# PG3_SHEET1.net
KiCad netlist of a schematic drawn in Altium Designer
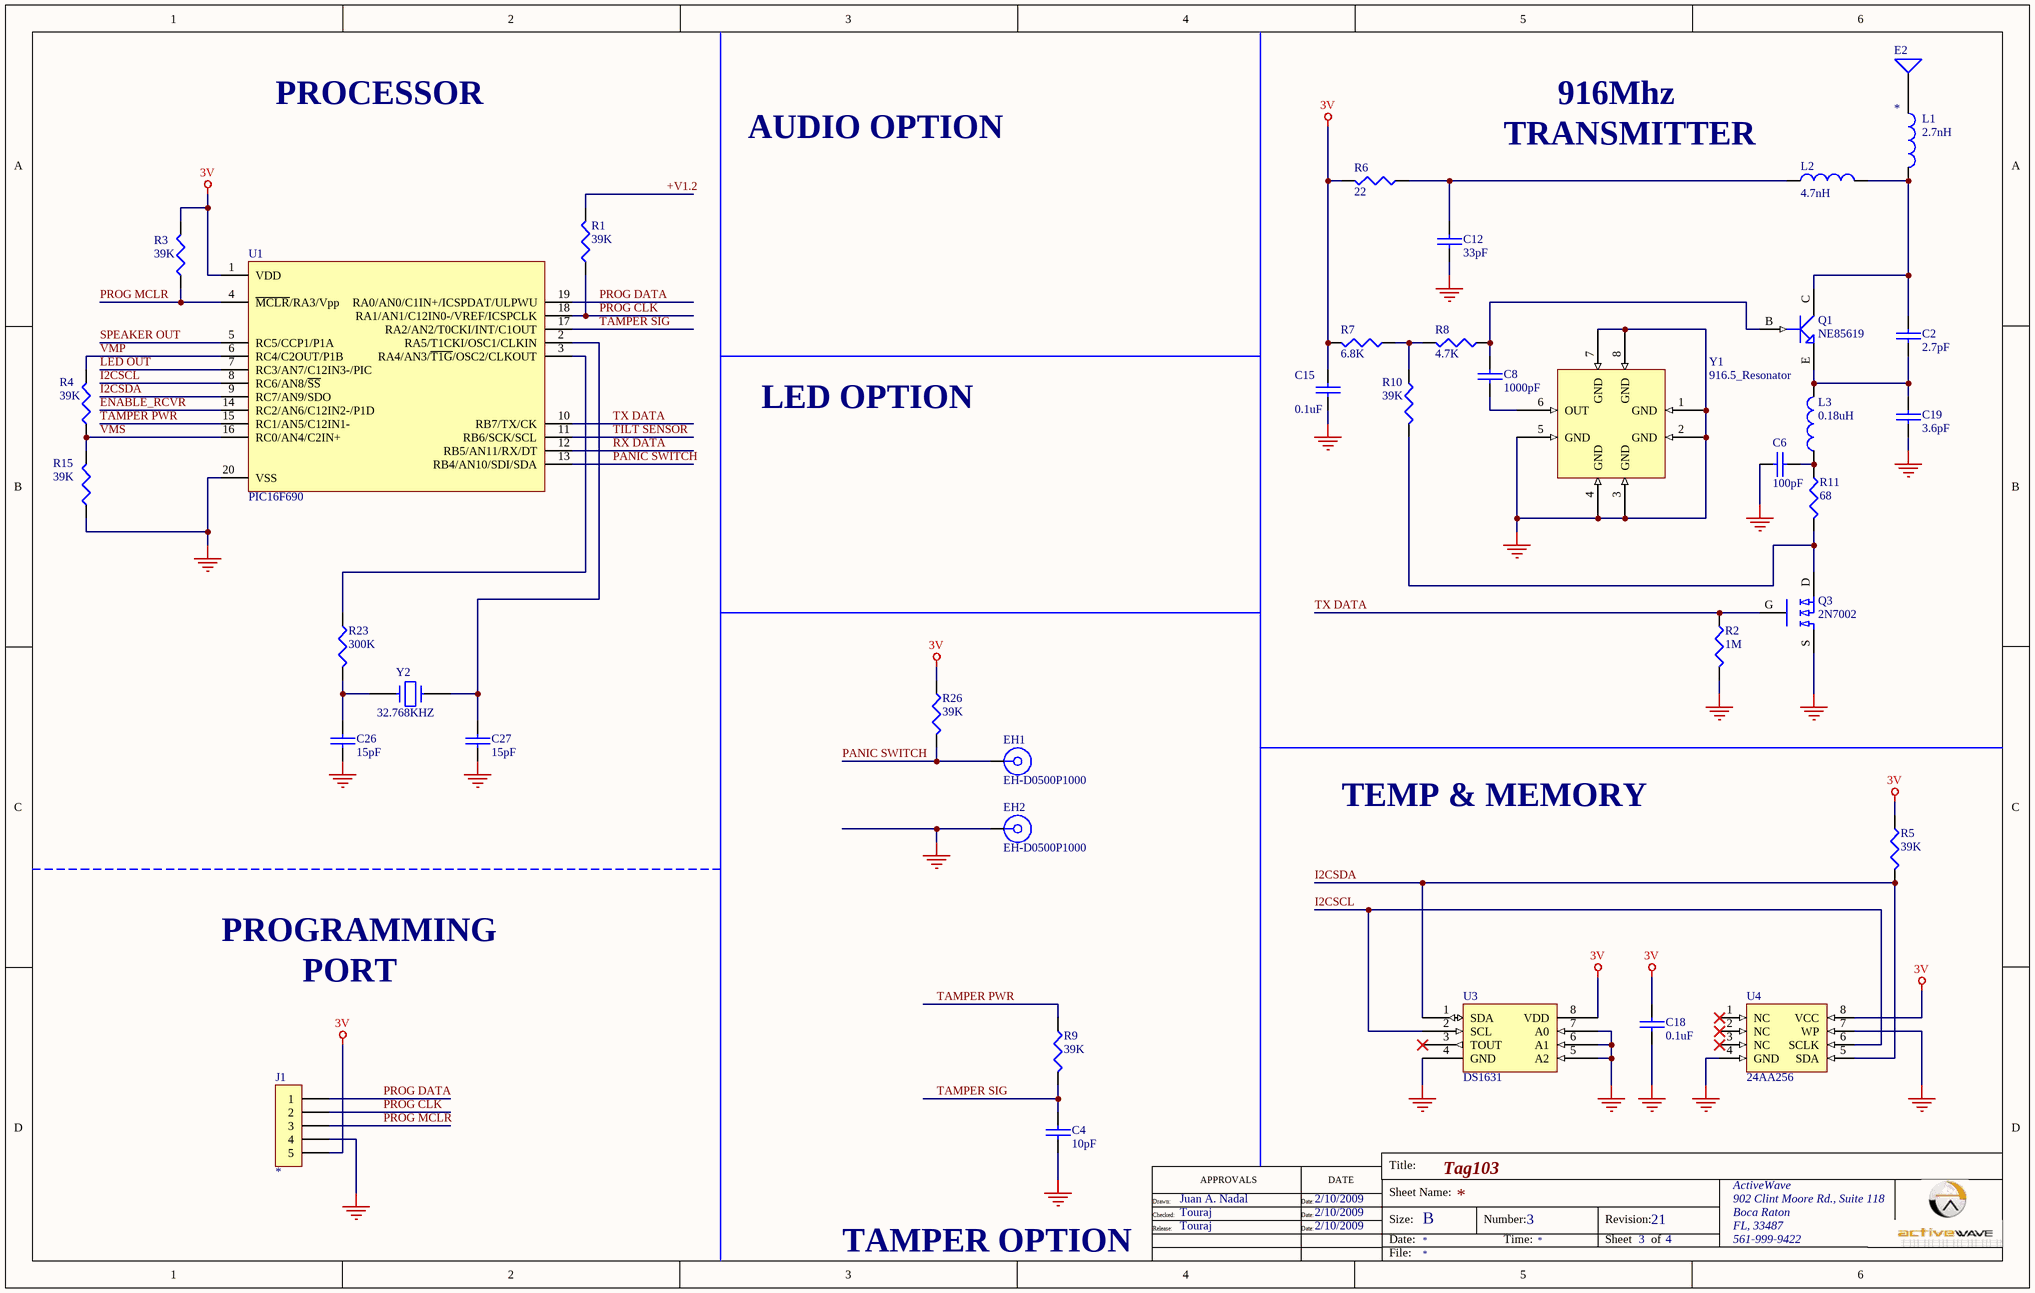
[diagram p0: PG3 SHEET1.schdoc]

(export (version "E")
  (design (tool "Eeschema 10.0.6"))
  (components
    (comp (ref "C2")
      (value "2.7pF")
      (footprint "0603")
      (description "Capacitor")
      (fields (field (name "Comment") "2 PF"))
      (libsource (lib "ActiveWave MasterLib") (part "CAP-0603"))
    )
    (comp (ref "C4")
      (value "10pF")
      (footprint "0603")
      (description "Capacitor")
      (libsource (lib "ActiveWave MasterLib") (part "CAP-0603"))
    )
    (comp (ref "C6")
      (value "100pF")
      (footprint "0603")
      (description "Capacitor")
      (fields (field (name "Comment") "100 pF"))
      (libsource (lib "ActiveWave MasterLib") (part "CAP-0603"))
    )
    (comp (ref "C8")
      (value "1000pF")
      (footprint "0603")
      (description "Capacitor")
      (fields (field (name "Comment") "1000 pF"))
      (libsource (lib "ActiveWave MasterLib") (part "CAP-0603"))
    )
    (comp (ref "C12")
      (value "33pF")
      (footprint "0603")
      (description "Capacitor")
      (fields (field (name "Comment") "33 pF"))
      (libsource (lib "ActiveWave MasterLib") (part "CAP-0603"))
    )
    (comp (ref "C15")
      (value "0.1uF")
      (footprint "0603")
      (description "Capacitor")
      (fields (field (name "Comment") "0.1 uF"))
      (libsource (lib "ActiveWave MasterLib") (part "CAP-0603"))
    )
    (comp (ref "C18")
      (value "0.1uF")
      (footprint "0603")
      (description "Capacitor")
      (fields (field (name "Comment") "0.1 uF"))
      (libsource (lib "ActiveWave MasterLib") (part "CAP-0603"))
    )
    (comp (ref "C19")
      (value "3.6pF")
      (footprint "0603")
      (description "Capacitor")
      (fields (field (name "Comment") "2.7 pF"))
      (libsource (lib "ActiveWave MasterLib") (part "CAP-0603"))
    )
    (comp (ref "C26")
      (value "15pF")
      (footprint "0603")
      (description "Capacitor")
      (libsource (lib "ActiveWave MasterLib") (part "CAP-0603"))
    )
    (comp (ref "C27")
      (value "15pF")
      (footprint "0603")
      (description "Capacitor")
      (libsource (lib "ActiveWave MasterLib") (part "CAP-0603"))
    )
    (comp (ref "E2")
      (value "*")
      (footprint "Antenna1")
      (fields (field (name "PART-VALUE") "*"))
      (libsource (lib "ActiveWave MasterLib") (part "Antenna1"))
    )
    (comp (ref "EH1")
      (value "EH-D0500P1000")
      (footprint "EH_D0500P1000")
      (fields (field (name "ITEM-DESCRIPTION") "EH-D0500P1000"))
      (libsource (lib "ActiveWave MasterLib") (part "E-HOLE"))
    )
    (comp (ref "EH2")
      (value "EH-D0500P1000")
      (footprint "EH_D0500P1000")
      (fields (field (name "ITEM-DESCRIPTION") "EH-D0500P1000"))
      (libsource (lib "ActiveWave MasterLib") (part "E-HOLE"))
    )
    (comp (ref "J1")
      (value "1X5 HEADER")
      (footprint "CONN5")
      (description "Connector")
      (fields (field (name "PART-VALUE") "*"))
      (libsource (lib "ActiveWave MasterLib") (part "CON5"))
    )
    (comp (ref "L1")
      (value "2.7nH")
      (footprint "0603")
      (libsource (lib "ActiveWave MasterLib") (part "INDUCTOR"))
    )
    (comp (ref "L2")
      (value "4.7nH")
      (footprint "0603")
      (fields (field (name "Comment") "10nH"))
      (libsource (lib "ActiveWave MasterLib") (part "INDUCTOR"))
    )
    (comp (ref "L3")
      (value "0.18uH")
      (footprint "0603")
      (libsource (lib "ActiveWave MasterLib") (part "INDUCTOR"))
    )
    (comp (ref "Q1")
      (value "NE85619")
      (footprint "3 PIN ULTRA SUPER MINI MOLD")
      (description "NPN Transistor")
      (libsource (lib "ActiveWave MasterLib") (part "NE85619"))
    )
    (comp (ref "Q3")
      (value "2N7002")
      (footprint "SOT23 FET")
      (libsource (lib "ActiveWave MasterLib") (part "2N7002"))
    )
    (comp (ref "R1")
      (value "39K")
      (footprint "0603")
      (libsource (lib "ActiveWave MasterLib") (part "RES-0603"))
    )
    (comp (ref "R2")
      (value "1M")
      (fields (field (name "Comment") "1 M"))
      (libsource (lib "ActiveWave MasterLib") (part "RES-0402"))
    )
    (comp (ref "R3")
      (value "39K")
      (footprint "0603")
      (libsource (lib "ActiveWave MasterLib") (part "RES-0603"))
    )
    (comp (ref "R4")
      (value "39K")
      (footprint "0603")
      (libsource (lib "ActiveWave MasterLib") (part "RES-0603"))
    )
    (comp (ref "R5")
      (value "39K")
      (footprint "0603")
      (libsource (lib "ActiveWave MasterLib") (part "RES-0603"))
    )
    (comp (ref "R6") (value "22") (libsource (lib "ActiveWave MasterLib") (part "RES-0402")))
    (comp (ref "R7") (value "6.8K") (libsource (lib "ActiveWave MasterLib") (part "RES-0402")))
    (comp (ref "R8")
      (value "4.7K")
      (fields (field (name "Comment") "4.7 K"))
      (libsource (lib "ActiveWave MasterLib") (part "RES-0402"))
    )
    (comp (ref "R9")
      (value "39K")
      (footprint "0603")
      (libsource (lib "ActiveWave MasterLib") (part "RES-0603"))
    )
    (comp (ref "R10")
      (value "39K")
      (footprint "0603")
      (libsource (lib "ActiveWave MasterLib") (part "RES-0603"))
    )
    (comp (ref "R11") (value "68") (libsource (lib "ActiveWave MasterLib") (part "RES-0402")))
    (comp (ref "R15")
      (value "39K")
      (footprint "0603")
      (libsource (lib "ActiveWave MasterLib") (part "RES-0603"))
    )
    (comp (ref "R23")
      (value "300K")
      (footprint "0603")
      (libsource (lib "ActiveWave MasterLib") (part "RES-0603"))
    )
    (comp (ref "R26")
      (value "39K")
      (footprint "0603")
      (fields (field (name "Comment") "4.7M"))
      (libsource (lib "ActiveWave MasterLib") (part "RES-0603"))
    )
    (comp (ref "U1")
      (value "PIC16F690")
      (footprint "SSOP20 WIDE")
      (libsource (lib "ActiveWave MasterLib") (part "PIC16F690"))
    )
    (comp (ref "U3")
      (value "DS1631")
      (footprint "SO8 SMALL")
      (libsource (lib "ActiveWave MasterLib") (part "DS1631"))
    )
    (comp (ref "U4")
      (value "24AA256")
      (footprint "SO8")
      (libsource (lib "ActiveWave MasterLib") (part "24AA256"))
    )
    (comp (ref "Y1")
      (value "916.5_Resonator")
      (footprint "RESONATOR")
      (libsource (lib "ActiveWave MasterLib") (part "RESONATOR"))
    )
    (comp (ref "Y2")
      (value "32.768KHZ")
      (footprint "CRYSTAL ABRACON ABS07")
      (description "Crystal")
      (fields (field (name "Comment") "32.768KHZ CRYSTAL"))
      (libsource (lib "ActiveWave MasterLib") (part "CRYSTAL"))
    )
  )
  (nets
    (net (code "1") (name "/+V1.2") (class "Default")
      (node (ref "R1") (pin "2") (pinfunction "2_2") (pintype "passive"))
    )
    (net (code "2") (name "/ENABLE_RCVR") (class "Default")
      (node (ref "U1") (pin "14") (pinfunction "RC2/AN6/C12IN2-/P1D_14") (pintype "passive"))
    )
    (net (code "3") (name "/I2CSCL") (class "Default")
      (node (ref "U1") (pin "8") (pinfunction "RC6/AN8/~{SS}_8") (pintype "passive"))
      (node (ref "U3") (pin "2") (pinfunction "SCL_2") (pintype "input"))
      (node (ref "U4") (pin "6") (pinfunction "SCLK_6") (pintype "input"))
    )
    (net (code "4") (name "/I2CSDA") (class "Default")
      (node (ref "R5") (pin "2") (pinfunction "2_2") (pintype "passive"))
      (node (ref "U1") (pin "9") (pinfunction "RC7/AN9/SDO_9") (pintype "passive"))
      (node (ref "U3") (pin "1") (pinfunction "SDA_1") (pintype "bidirectional"))
      (node (ref "U4") (pin "5") (pinfunction "SDA_5") (pintype "input"))
    )
    (net (code "5") (name "/LED OUT") (class "Default")
      (node (ref "U1") (pin "7") (pinfunction "RC3/AN7/C12IN3-/PIC_7") (pintype "passive"))
    )
    (net (code "6") (name "/PANIC SWITCH") (class "Default")
      (node (ref "EH1") (pin "1") (pinfunction "1_1") (pintype "passive"))
      (node (ref "R26") (pin "2") (pinfunction "2_2") (pintype "passive"))
      (node (ref "U1") (pin "13") (pinfunction "RB4/AN10/SDI/SDA_13") (pintype "passive"))
    )
    (net (code "7") (name "/PROG CLK") (class "Default")
      (node (ref "J1") (pin "2") (pinfunction "2_2") (pintype "passive"))
      (node (ref "R1") (pin "1") (pinfunction "1_1") (pintype "passive"))
      (node (ref "U1") (pin "18") (pinfunction "RA1/AN1/C12IN0-/VREF/ICSPCLK_18") (pintype "passive"))
    )
    (net (code "8") (name "/PROG DATA") (class "Default")
      (node (ref "J1") (pin "1") (pinfunction "1_1") (pintype "passive"))
      (node (ref "U1") (pin "19") (pinfunction "RA0/AN0/C1IN+/ICSPDAT/ULPWU_19") (pintype "passive"))
    )
    (net (code "9") (name "/PROG MCLR") (class "Default")
      (node (ref "J1") (pin "3") (pinfunction "3_3") (pintype "passive"))
      (node (ref "R3") (pin "1") (pinfunction "1_1") (pintype "passive"))
      (node (ref "U1") (pin "4") (pinfunction "~{MCLR}/RA3/Vpp_4") (pintype "passive"))
    )
    (net (code "10") (name "/RX DATA") (class "Default")
      (node (ref "U1") (pin "12") (pinfunction "RB5/AN11/RX/DT_12") (pintype "passive"))
    )
    (net (code "11") (name "/SPEAKER OUT") (class "Default")
      (node (ref "U1") (pin "5") (pinfunction "RC5/CCP1/P1A_5") (pintype "passive"))
    )
    (net (code "12") (name "/TAMPER PWR") (class "Default")
      (node (ref "R9") (pin "1") (pinfunction "1_1") (pintype "passive"))
      (node (ref "U1") (pin "15") (pinfunction "RC1/AN5/C12IN1-_15") (pintype "passive"))
    )
    (net (code "13") (name "/TAMPER SIG") (class "Default")
      (node (ref "C4") (pin "1") (pinfunction "1_1") (pintype "passive"))
      (node (ref "R9") (pin "2") (pinfunction "2_2") (pintype "passive"))
      (node (ref "U1") (pin "17") (pinfunction "RA2/AN2/T0CKI/INT/C1OUT_17") (pintype "passive"))
    )
    (net (code "14") (name "/TILT SENSOR") (class "Default")
      (node (ref "U1") (pin "11") (pinfunction "RB6/SCK/SCL_11") (pintype "passive"))
    )
    (net (code "15") (name "/TX DATA") (class "Default")
      (node (ref "Q3") (pin "G") (pinfunction "G_G") (pintype "passive"))
      (node (ref "R2") (pin "1") (pinfunction "1_1") (pintype "passive"))
      (node (ref "U1") (pin "10") (pinfunction "RB7/TX/CK_10") (pintype "passive"))
    )
    (net (code "16") (name "/VMP") (class "Default")
      (node (ref "R4") (pin "2") (pinfunction "2_2") (pintype "passive"))
      (node (ref "U1") (pin "6") (pinfunction "RC4/C2OUT/P1B_6") (pintype "passive"))
    )
    (net (code "17") (name "/VMS") (class "Default")
      (node (ref "R15") (pin "2") (pinfunction "2_2") (pintype "passive"))
      (node (ref "R4") (pin "1") (pinfunction "1_1") (pintype "passive"))
      (node (ref "U1") (pin "16") (pinfunction "RC0/AN4/C2IN+_16") (pintype "passive"))
    )
    (net (code "18") (name "3V") (class "Default")
      (node (ref "C15") (pin "1") (pinfunction "1_1") (pintype "passive"))
      (node (ref "C18") (pin "1") (pinfunction "1_1") (pintype "passive"))
      (node (ref "J1") (pin "5") (pinfunction "5_5") (pintype "passive"))
      (node (ref "R26") (pin "1") (pinfunction "1_1") (pintype "passive"))
      (node (ref "R3") (pin "2") (pinfunction "2_2") (pintype "passive"))
      (node (ref "R5") (pin "1") (pinfunction "1_1") (pintype "passive"))
      (node (ref "R6") (pin "2") (pinfunction "2_2") (pintype "passive"))
      (node (ref "R7") (pin "2") (pinfunction "2_2") (pintype "passive"))
      (node (ref "U1") (pin "1") (pinfunction "VDD_1") (pintype "passive"))
      (node (ref "U3") (pin "8") (pinfunction "VDD_8") (pintype "power_in"))
      (node (ref "U4") (pin "8") (pinfunction "VCC_8") (pintype "input"))
    )
    (net (code "19") (name "GND") (class "Default")
      (node (ref "C12") (pin "2") (pinfunction "2_2") (pintype "passive"))
      (node (ref "C15") (pin "2") (pinfunction "2_2") (pintype "passive"))
      (node (ref "C18") (pin "2") (pinfunction "2_2") (pintype "passive"))
      (node (ref "C19") (pin "2") (pinfunction "2_2") (pintype "passive"))
      (node (ref "C26") (pin "2") (pinfunction "2_2") (pintype "passive"))
      (node (ref "C27") (pin "2") (pinfunction "2_2") (pintype "passive"))
      (node (ref "C4") (pin "2") (pinfunction "2_2") (pintype "passive"))
      (node (ref "C6") (pin "2") (pinfunction "2_2") (pintype "passive"))
      (node (ref "EH2") (pin "1") (pinfunction "1_1") (pintype "passive"))
      (node (ref "J1") (pin "4") (pinfunction "4_4") (pintype "passive"))
      (node (ref "Q3") (pin "S") (pinfunction "S_S") (pintype "passive"))
      (node (ref "R15") (pin "1") (pinfunction "1_1") (pintype "passive"))
      (node (ref "R2") (pin "2") (pinfunction "2_2") (pintype "passive"))
      (node (ref "U1") (pin "20") (pinfunction "VSS_20") (pintype "passive"))
      (node (ref "U3") (pin "4") (pinfunction "GND_4") (pintype "power_in"))
      (node (ref "U3") (pin "5") (pinfunction "A2_5") (pintype "input"))
      (node (ref "U3") (pin "6") (pinfunction "A1_6") (pintype "input"))
      (node (ref "U3") (pin "7") (pinfunction "A0_7") (pintype "input"))
      (node (ref "U4") (pin "4") (pinfunction "GND_4") (pintype "input"))
      (node (ref "U4") (pin "7") (pinfunction "WP_7") (pintype "input"))
      (node (ref "Y1") (pin "1") (pinfunction "GND_1") (pintype "input"))
      (node (ref "Y1") (pin "2") (pinfunction "GND_2") (pintype "input"))
      (node (ref "Y1") (pin "3") (pinfunction "GND_3") (pintype "input"))
      (node (ref "Y1") (pin "4") (pinfunction "GND_4") (pintype "input"))
      (node (ref "Y1") (pin "5") (pinfunction "GND_5") (pintype "input"))
      (node (ref "Y1") (pin "7") (pinfunction "GND_7") (pintype "input"))
      (node (ref "Y1") (pin "8") (pinfunction "GND_8") (pintype "input"))
    )
    (net (code "20") (name "Net-(C2-Pad1)") (class "Default")
      (node (ref "C2") (pin "1") (pinfunction "1_1") (pintype "passive"))
      (node (ref "L1") (pin "2") (pinfunction "2_2") (pintype "passive"))
      (node (ref "L2") (pin "2") (pinfunction "2_2") (pintype "passive"))
      (node (ref "Q1") (pin "C") (pinfunction "C_C") (pintype "passive"))
    )
    (net (code "21") (name "Net-(C6-Pad1)") (class "Default")
      (node (ref "C6") (pin "1") (pinfunction "1_1") (pintype "passive"))
      (node (ref "L3") (pin "1") (pinfunction "1_1") (pintype "passive"))
      (node (ref "R11") (pin "1") (pinfunction "1_1") (pintype "passive"))
    )
    (net (code "22") (name "Net-(C8-Pad1)") (class "Default")
      (node (ref "C8") (pin "1") (pinfunction "1_1") (pintype "passive"))
      (node (ref "Q1") (pin "B") (pinfunction "B_B") (pintype "input"))
      (node (ref "R8") (pin "1") (pinfunction "1_1") (pintype "passive"))
    )
    (net (code "23") (name "Net-(C12-Pad1)") (class "Default")
      (node (ref "C12") (pin "1") (pinfunction "1_1") (pintype "passive"))
      (node (ref "L2") (pin "1") (pinfunction "1_1") (pintype "passive"))
      (node (ref "R6") (pin "1") (pinfunction "1_1") (pintype "passive"))
    )
    (net (code "24") (name "Net-(C19-Pad1)") (class "Default")
      (node (ref "C19") (pin "1") (pinfunction "1_1") (pintype "passive"))
      (node (ref "C2") (pin "2") (pinfunction "2_2") (pintype "passive"))
      (node (ref "L3") (pin "2") (pinfunction "2_2") (pintype "passive"))
      (node (ref "Q1") (pin "E") (pinfunction "E_E") (pintype "passive"))
    )
    (net (code "25") (name "Net-(C26-Pad1)") (class "Default")
      (node (ref "C26") (pin "1") (pinfunction "1_1") (pintype "passive"))
      (node (ref "R23") (pin "2") (pinfunction "2_2") (pintype "passive"))
      (node (ref "Y2") (pin "1") (pinfunction "1_1") (pintype "passive"))
    )
    (net (code "26") (name "Net-(E2-Pad1)") (class "Default")
      (node (ref "E2") (pin "1") (pinfunction "1_1") (pintype "passive"))
      (node (ref "L1") (pin "1") (pinfunction "1_1") (pintype "passive"))
    )
    (net (code "27") (name "Net-(Q3-PadD)") (class "Default")
      (node (ref "Q3") (pin "D") (pinfunction "D_D") (pintype "passive"))
      (node (ref "R10") (pin "2") (pinfunction "2_2") (pintype "passive"))
      (node (ref "R11") (pin "2") (pinfunction "2_2") (pintype "passive"))
    )
    (net (code "28") (name "Net-(R10-Pad1)") (class "Default")
      (node (ref "R10") (pin "1") (pinfunction "1_1") (pintype "passive"))
      (node (ref "R7") (pin "1") (pinfunction "1_1") (pintype "passive"))
      (node (ref "R8") (pin "2") (pinfunction "2_2") (pintype "passive"))
    )
    (net (code "29") (name "Net-(U1-RA4{slash}AN3{slash}~{T1G}{slash}OSC2{slash}CLKOUT)") (class "Default")
      (node (ref "R23") (pin "1") (pinfunction "1_1") (pintype "passive"))
      (node (ref "U1") (pin "3") (pinfunction "RA4/AN3/~{T1G}/OSC2/CLKOUT_3") (pintype "passive"))
    )
    (net (code "30") (name "Net-(U1-RA5{slash}T1CKI{slash}OSC1{slash}CLKIN)") (class "Default")
      (node (ref "C27") (pin "1") (pinfunction "1_1") (pintype "passive"))
      (node (ref "U1") (pin "2") (pinfunction "RA5/T1CKI/OSC1/CLKIN_2") (pintype "passive"))
      (node (ref "Y2") (pin "2") (pinfunction "2_2") (pintype "passive"))
    )
    (net (code "31") (name "Net-(Y1-OUT)") (class "Default")
      (node (ref "C8") (pin "2") (pinfunction "2_2") (pintype "passive"))
      (node (ref "Y1") (pin "6") (pinfunction "OUT_6") (pintype "input"))
    )
    (net (code "32") (name "unconnected-(U3-TOUT-Pad3)") (class "Default")
      (node (ref "U3") (pin "3") (pinfunction "TOUT_3") (pintype "output+no_connect"))
    )
    (net (code "33") (name "unconnected-(U4-NC-Pad1)") (class "Default")
      (node (ref "U4") (pin "1") (pinfunction "NC_1") (pintype "input+no_connect"))
    )
    (net (code "34") (name "unconnected-(U4-NC-Pad2)") (class "Default")
      (node (ref "U4") (pin "2") (pinfunction "NC_2") (pintype "input+no_connect"))
    )
    (net (code "35") (name "unconnected-(U4-NC-Pad3)") (class "Default")
      (node (ref "U4") (pin "3") (pinfunction "NC_3") (pintype "input+no_connect"))
    )
  )
)
